# stewduino.net
KiCad netlist of a schematic drawn in EAGLE
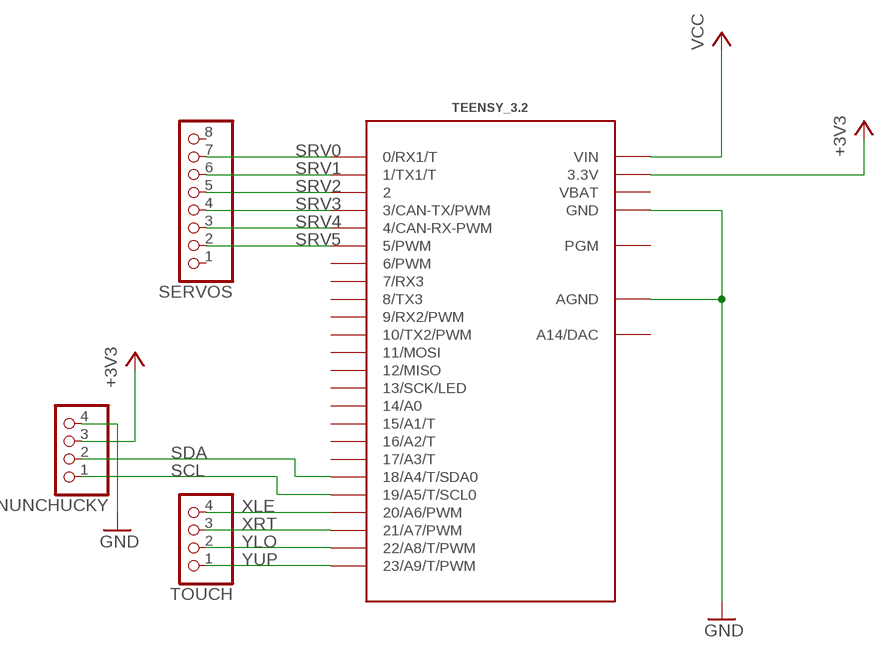
[diagram p0: schematic, sheet 1]

(export (version "E")
  (design (tool "Eeschema 10.0.6"))
  (components
    (comp (ref "NUNCHUCKY")
      (value "PINHD-1X4")
      (footprint "eagle-import:1X04")
      (libsource (lib "eagle-import") (part "PINHD-1X4"))
    )
    (comp (ref "SERVOS")
      (value "PINHD-1X8")
      (footprint "eagle-import:1X08")
      (libsource (lib "eagle-import") (part "PINHD-1X8"))
    )
    (comp (ref "TEENSY_3.2")
      (value "TEENSY_3.1-3.2_OUTER_ROW")
      (footprint "eagle-import:TEENSY_3.0-3.2&LC_OUTER_ROW")
      (libsource (lib "eagle-import") (part "TEENSY_3.1-3.2_OUTER_ROW"))
    )
    (comp (ref "TOUCH")
      (value "PINHD-1X4")
      (footprint "eagle-import:1X04")
      (libsource (lib "eagle-import") (part "PINHD-1X4"))
    )
  )
  (nets
    (net (code "1") (name "+3V3") (class "Default")
      (node (ref "NUNCHUCKY") (pin "3") (pinfunction "3_3") (pintype "passive"))
      (node (ref "TEENSY_3.2") (pin "3.3V") (pinfunction "3.3V_3.3V") (pintype "power_in"))
      (node (ref "TEENSY_3.2") (pin "3.3V1") (pinfunction "3.3V_3.3V1") (pintype "power_in"))
    )
    (net (code "2") (name "/SCL") (class "Default")
      (node (ref "NUNCHUCKY") (pin "1") (pinfunction "1_1") (pintype "passive"))
      (node (ref "TEENSY_3.2") (pin "19/A5") (pinfunction "19/A5/T/SCL0_19/A5") (pintype "bidirectional"))
    )
    (net (code "3") (name "/SDA") (class "Default")
      (node (ref "NUNCHUCKY") (pin "2") (pinfunction "2_2") (pintype "passive"))
      (node (ref "TEENSY_3.2") (pin "18/A4") (pinfunction "18/A4/T/SDA0_18/A4") (pintype "bidirectional"))
    )
    (net (code "4") (name "/SRV0") (class "Default")
      (node (ref "SERVOS") (pin "7") (pinfunction "7_7") (pintype "passive"))
      (node (ref "TEENSY_3.2") (pin "0") (pinfunction "0/RX1/T_0") (pintype "bidirectional"))
    )
    (net (code "5") (name "/SRV1") (class "Default")
      (node (ref "SERVOS") (pin "6") (pinfunction "6_6") (pintype "passive"))
      (node (ref "TEENSY_3.2") (pin "1") (pinfunction "1/TX1/T_1") (pintype "bidirectional"))
    )
    (net (code "6") (name "/SRV2") (class "Default")
      (node (ref "SERVOS") (pin "5") (pinfunction "5_5") (pintype "passive"))
      (node (ref "TEENSY_3.2") (pin "2") (pinfunction "2_2") (pintype "bidirectional"))
    )
    (net (code "7") (name "/SRV3") (class "Default")
      (node (ref "SERVOS") (pin "4") (pinfunction "4_4") (pintype "passive"))
      (node (ref "TEENSY_3.2") (pin "3") (pinfunction "3/CAN-TX/PWM_3") (pintype "bidirectional"))
    )
    (net (code "8") (name "/SRV4") (class "Default")
      (node (ref "SERVOS") (pin "3") (pinfunction "3_3") (pintype "passive"))
      (node (ref "TEENSY_3.2") (pin "4") (pinfunction "4/CAN-RX-PWM_4") (pintype "bidirectional"))
    )
    (net (code "9") (name "/SRV5") (class "Default")
      (node (ref "SERVOS") (pin "2") (pinfunction "2_2") (pintype "passive"))
      (node (ref "TEENSY_3.2") (pin "5") (pinfunction "5/PWM_5") (pintype "bidirectional"))
    )
    (net (code "10") (name "/VBAT") (class "Default")
      (node (ref "TEENSY_3.2") (pin "VBAT") (pinfunction "VBAT_VBAT") (pintype "power_in"))
    )
    (net (code "11") (name "/XLE") (class "Default")
      (node (ref "TEENSY_3.2") (pin "20/A6") (pinfunction "20/A6/PWM_20/A6") (pintype "bidirectional"))
      (node (ref "TOUCH") (pin "4") (pinfunction "4_4") (pintype "passive"))
    )
    (net (code "12") (name "/XRT") (class "Default")
      (node (ref "TEENSY_3.2") (pin "21/A7") (pinfunction "21/A7/PWM_21/A7") (pintype "bidirectional"))
      (node (ref "TOUCH") (pin "3") (pinfunction "3_3") (pintype "passive"))
    )
    (net (code "13") (name "/YLO") (class "Default")
      (node (ref "TEENSY_3.2") (pin "22/A8") (pinfunction "22/A8/T/PWM_22/A8") (pintype "bidirectional"))
      (node (ref "TOUCH") (pin "2") (pinfunction "2_2") (pintype "passive"))
    )
    (net (code "14") (name "/YUP") (class "Default")
      (node (ref "TEENSY_3.2") (pin "23/A9") (pinfunction "23/A9/T/PWM_23/A9") (pintype "bidirectional"))
      (node (ref "TOUCH") (pin "1") (pinfunction "1_1") (pintype "passive"))
    )
    (net (code "15") (name "GND") (class "Default")
      (node (ref "NUNCHUCKY") (pin "4") (pinfunction "4_4") (pintype "passive"))
      (node (ref "TEENSY_3.2") (pin "AGND") (pinfunction "AGND_AGND") (pintype "power_in"))
      (node (ref "TEENSY_3.2") (pin "GND") (pinfunction "GND_GND") (pintype "power_in"))
      (node (ref "TEENSY_3.2") (pin "GND1") (pinfunction "GND_GND1") (pintype "power_in"))
    )
    (net (code "16") (name "VCC") (class "Default")
      (node (ref "TEENSY_3.2") (pin "VIN") (pinfunction "VIN_VIN") (pintype "power_in"))
    )
    (net (code "17") (name "unconnected-(SERVOS-Pad1)") (class "Default")
      (node (ref "SERVOS") (pin "1") (pinfunction "1_1") (pintype "passive"))
    )
    (net (code "18") (name "unconnected-(SERVOS-Pad8)") (class "Default")
      (node (ref "SERVOS") (pin "8") (pinfunction "8_8") (pintype "passive"))
    )
    (net (code "19") (name "unconnected-(TEENSY_3.2-6{slash}PWM-Pad6)") (class "Default")
      (node (ref "TEENSY_3.2") (pin "6") (pinfunction "6/PWM_6") (pintype "bidirectional"))
    )
    (net (code "20") (name "unconnected-(TEENSY_3.2-7{slash}RX3-Pad7)") (class "Default")
      (node (ref "TEENSY_3.2") (pin "7") (pinfunction "7/RX3_7") (pintype "bidirectional"))
    )
    (net (code "21") (name "unconnected-(TEENSY_3.2-8{slash}TX3-Pad8)") (class "Default")
      (node (ref "TEENSY_3.2") (pin "8") (pinfunction "8/TX3_8") (pintype "bidirectional"))
    )
    (net (code "22") (name "unconnected-(TEENSY_3.2-9{slash}RX2{slash}PWM-Pad9)") (class "Default")
      (node (ref "TEENSY_3.2") (pin "9") (pinfunction "9/RX2/PWM_9") (pintype "bidirectional"))
    )
    (net (code "23") (name "unconnected-(TEENSY_3.2-10{slash}TX2{slash}PWM-Pad10)") (class "Default")
      (node (ref "TEENSY_3.2") (pin "10") (pinfunction "10/TX2/PWM_10") (pintype "bidirectional"))
    )
    (net (code "24") (name "unconnected-(TEENSY_3.2-11{slash}MOSI-Pad11)") (class "Default")
      (node (ref "TEENSY_3.2") (pin "11") (pinfunction "11/MOSI_11") (pintype "bidirectional"))
    )
    (net (code "25") (name "unconnected-(TEENSY_3.2-12{slash}MISO-Pad12)") (class "Default")
      (node (ref "TEENSY_3.2") (pin "12") (pinfunction "12/MISO_12") (pintype "bidirectional"))
    )
    (net (code "26") (name "unconnected-(TEENSY_3.2-13{slash}SCK{slash}LED-Pad13)") (class "Default")
      (node (ref "TEENSY_3.2") (pin "13") (pinfunction "13/SCK/LED_13") (pintype "bidirectional"))
    )
    (net (code "27") (name "unconnected-(TEENSY_3.2-15{slash}A1{slash}T-Pad15{slash}A1)") (class "Default")
      (node (ref "TEENSY_3.2") (pin "15/A1") (pinfunction "15/A1/T_15/A1") (pintype "bidirectional"))
    )
    (net (code "28") (name "unconnected-(TEENSY_3.2-16{slash}A2{slash}T-Pad16{slash}A2)") (class "Default")
      (node (ref "TEENSY_3.2") (pin "16/A2") (pinfunction "16/A2/T_16/A2") (pintype "bidirectional"))
    )
    (net (code "29") (name "unconnected-(TEENSY_3.2-17{slash}A3{slash}T-Pad17{slash}A3)") (class "Default")
      (node (ref "TEENSY_3.2") (pin "17/A3") (pinfunction "17/A3/T_17/A3") (pintype "bidirectional"))
    )
    (net (code "30") (name "unconnected-(TEENSY_3.2-A14{slash}DAC-PadRESET{slash}DAC)") (class "Default")
      (node (ref "TEENSY_3.2") (pin "RESET/DAC") (pinfunction "A14/DAC_RESET/DAC") (pintype "bidirectional"))
    )
    (net (code "31") (name "unconnected-(TEENSY_3.2-Pad14{slash}A0)") (class "Default")
      (node (ref "TEENSY_3.2") (pin "14/A0") (pinfunction "14/A0_14/A0") (pintype "bidirectional"))
    )
    (net (code "32") (name "unconnected-(TEENSY_3.2-PadPGM)") (class "Default")
      (node (ref "TEENSY_3.2") (pin "PGM") (pinfunction "PGM_PGM") (pintype "bidirectional"))
    )
  )
)
